# oscilateur.net
KiCad netlist of a schematic drawn in EAGLE
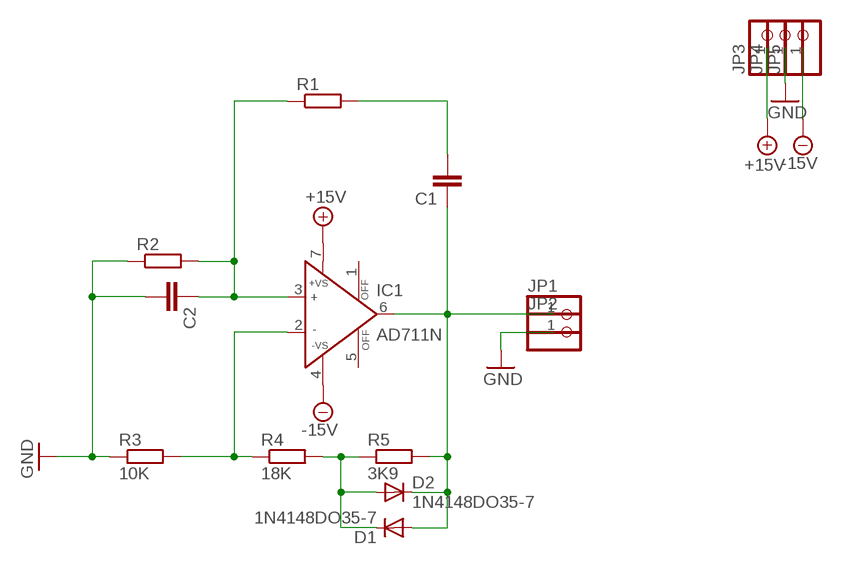
[diagram p0: schematic, sheet 1]

(export (version "E")
  (design (tool "Eeschema 10.0.6"))
  (components
    (comp (ref "C1")
      (value "C-EU075-032X103")
      (footprint "eagle-import:C075-032X103")
      (libsource (lib "eagle-import") (part "C-EU075-032X103"))
    )
    (comp (ref "C2")
      (value "C-EU075-032X103")
      (footprint "eagle-import:C075-032X103")
      (libsource (lib "eagle-import") (part "C-EU075-032X103"))
    )
    (comp (ref "D1")
      (value "1N4148DO35-7")
      (footprint "eagle-import:DO35-7")
      (libsource (lib "eagle-import") (part "1N4148DO35-7"))
    )
    (comp (ref "D2")
      (value "1N4148DO35-7")
      (footprint "eagle-import:DO35-7")
      (libsource (lib "eagle-import") (part "1N4148DO35-7"))
    )
    (comp (ref "IC1")
      (value "AD711N")
      (footprint "eagle-import:DIL08")
      (fields (field (name "MPN") "AD711BQ"))
      (libsource (lib "eagle-import") (part "AD711N"))
    )
    (comp (ref "JP1")
      (value "PINHD-1X1")
      (footprint "eagle-import:1X01")
      (libsource (lib "eagle-import") (part "PINHD-1X1"))
    )
    (comp (ref "JP2")
      (value "PINHD-1X1")
      (footprint "eagle-import:1X01")
      (libsource (lib "eagle-import") (part "PINHD-1X1"))
    )
    (comp (ref "JP3")
      (value "PINHD-1X1")
      (footprint "eagle-import:1X01")
      (libsource (lib "eagle-import") (part "PINHD-1X1"))
    )
    (comp (ref "JP4")
      (value "PINHD-1X1")
      (footprint "eagle-import:1X01")
      (libsource (lib "eagle-import") (part "PINHD-1X1"))
    )
    (comp (ref "JP5")
      (value "PINHD-1X1")
      (footprint "eagle-import:1X01")
      (libsource (lib "eagle-import") (part "PINHD-1X1"))
    )
    (comp (ref "R1")
      (value "R-EU_0204/7")
      (footprint "eagle-import:0204_7")
      (libsource (lib "eagle-import") (part "R-EU_0204/7"))
    )
    (comp (ref "R2")
      (value "R-EU_0204/7")
      (footprint "eagle-import:0204_7")
      (libsource (lib "eagle-import") (part "R-EU_0204/7"))
    )
    (comp (ref "R3")
      (value "10K")
      (footprint "eagle-import:0204_7")
      (libsource (lib "eagle-import") (part "R-EU_0204/7"))
    )
    (comp (ref "R4")
      (value "18K")
      (footprint "eagle-import:0204_7")
      (libsource (lib "eagle-import") (part "R-EU_0204/7"))
    )
    (comp (ref "R5")
      (value "3K9")
      (footprint "eagle-import:0204_7")
      (libsource (lib "eagle-import") (part "R-EU_0204/7"))
    )
  )
  (nets
    (net (code "1") (name "+15V") (class "Default")
      (node (ref "IC1") (pin "7") (pinfunction "+VS_7") (pintype "input"))
      (node (ref "JP3") (pin "1") (pinfunction "1_1") (pintype "passive"))
    )
    (net (code "2") (name "-15V") (class "Default")
      (node (ref "IC1") (pin "4") (pinfunction "-VS_4") (pintype "input"))
      (node (ref "JP5") (pin "1") (pinfunction "1_1") (pintype "passive"))
    )
    (net (code "3") (name "GND") (class "Default")
      (node (ref "C2") (pin "2") (pinfunction "2_2") (pintype "passive"))
      (node (ref "JP2") (pin "1") (pinfunction "1_1") (pintype "passive"))
      (node (ref "JP4") (pin "1") (pinfunction "1_1") (pintype "passive"))
      (node (ref "R2") (pin "1") (pinfunction "1_1") (pintype "passive"))
      (node (ref "R3") (pin "1") (pinfunction "1_1") (pintype "passive"))
    )
    (net (code "4") (name "Net-(C1-Pad2)") (class "Default")
      (node (ref "C1") (pin "2") (pinfunction "2_2") (pintype "passive"))
      (node (ref "R1") (pin "2") (pinfunction "2_2") (pintype "passive"))
    )
    (net (code "5") (name "Net-(D1-PadC)") (class "Default")
      (node (ref "D1") (pin "C") (pinfunction "C_C") (pintype "passive"))
      (node (ref "D2") (pin "A") (pinfunction "A_A") (pintype "passive"))
      (node (ref "R4") (pin "2") (pinfunction "2_2") (pintype "passive"))
      (node (ref "R5") (pin "1") (pinfunction "1_1") (pintype "passive"))
    )
    (net (code "6") (name "Net-(IC1-IN+)") (class "Default")
      (node (ref "C2") (pin "1") (pinfunction "1_1") (pintype "passive"))
      (node (ref "IC1") (pin "3") (pinfunction "IN+_3") (pintype "input"))
      (node (ref "R1") (pin "1") (pinfunction "1_1") (pintype "passive"))
      (node (ref "R2") (pin "2") (pinfunction "2_2") (pintype "passive"))
    )
    (net (code "7") (name "Net-(IC1-IN-)") (class "Default")
      (node (ref "IC1") (pin "2") (pinfunction "IN-_2") (pintype "input"))
      (node (ref "R3") (pin "2") (pinfunction "2_2") (pintype "passive"))
      (node (ref "R4") (pin "1") (pinfunction "1_1") (pintype "passive"))
    )
    (net (code "8") (name "Net-(IC1-OUT)") (class "Default")
      (node (ref "C1") (pin "1") (pinfunction "1_1") (pintype "passive"))
      (node (ref "D1") (pin "A") (pinfunction "A_A") (pintype "passive"))
      (node (ref "D2") (pin "C") (pinfunction "C_C") (pintype "passive"))
      (node (ref "IC1") (pin "6") (pinfunction "OUT_6") (pintype "output"))
      (node (ref "JP1") (pin "1") (pinfunction "1_1") (pintype "passive"))
      (node (ref "R5") (pin "2") (pinfunction "2_2") (pintype "passive"))
    )
    (net (code "9") (name "unconnected-(IC1-OFF-Pad1)") (class "Default")
      (node (ref "IC1") (pin "1") (pinfunction "OFF_1") (pintype "passive"))
    )
    (net (code "10") (name "unconnected-(IC1-OFF-Pad5)") (class "Default")
      (node (ref "IC1") (pin "5") (pinfunction "OFF_5") (pintype "passive"))
    )
  )
)
